# 1-Schematic_Automatic_temperature_humidi.net
KiCad netlist of a schematic drawn in EasyEDA
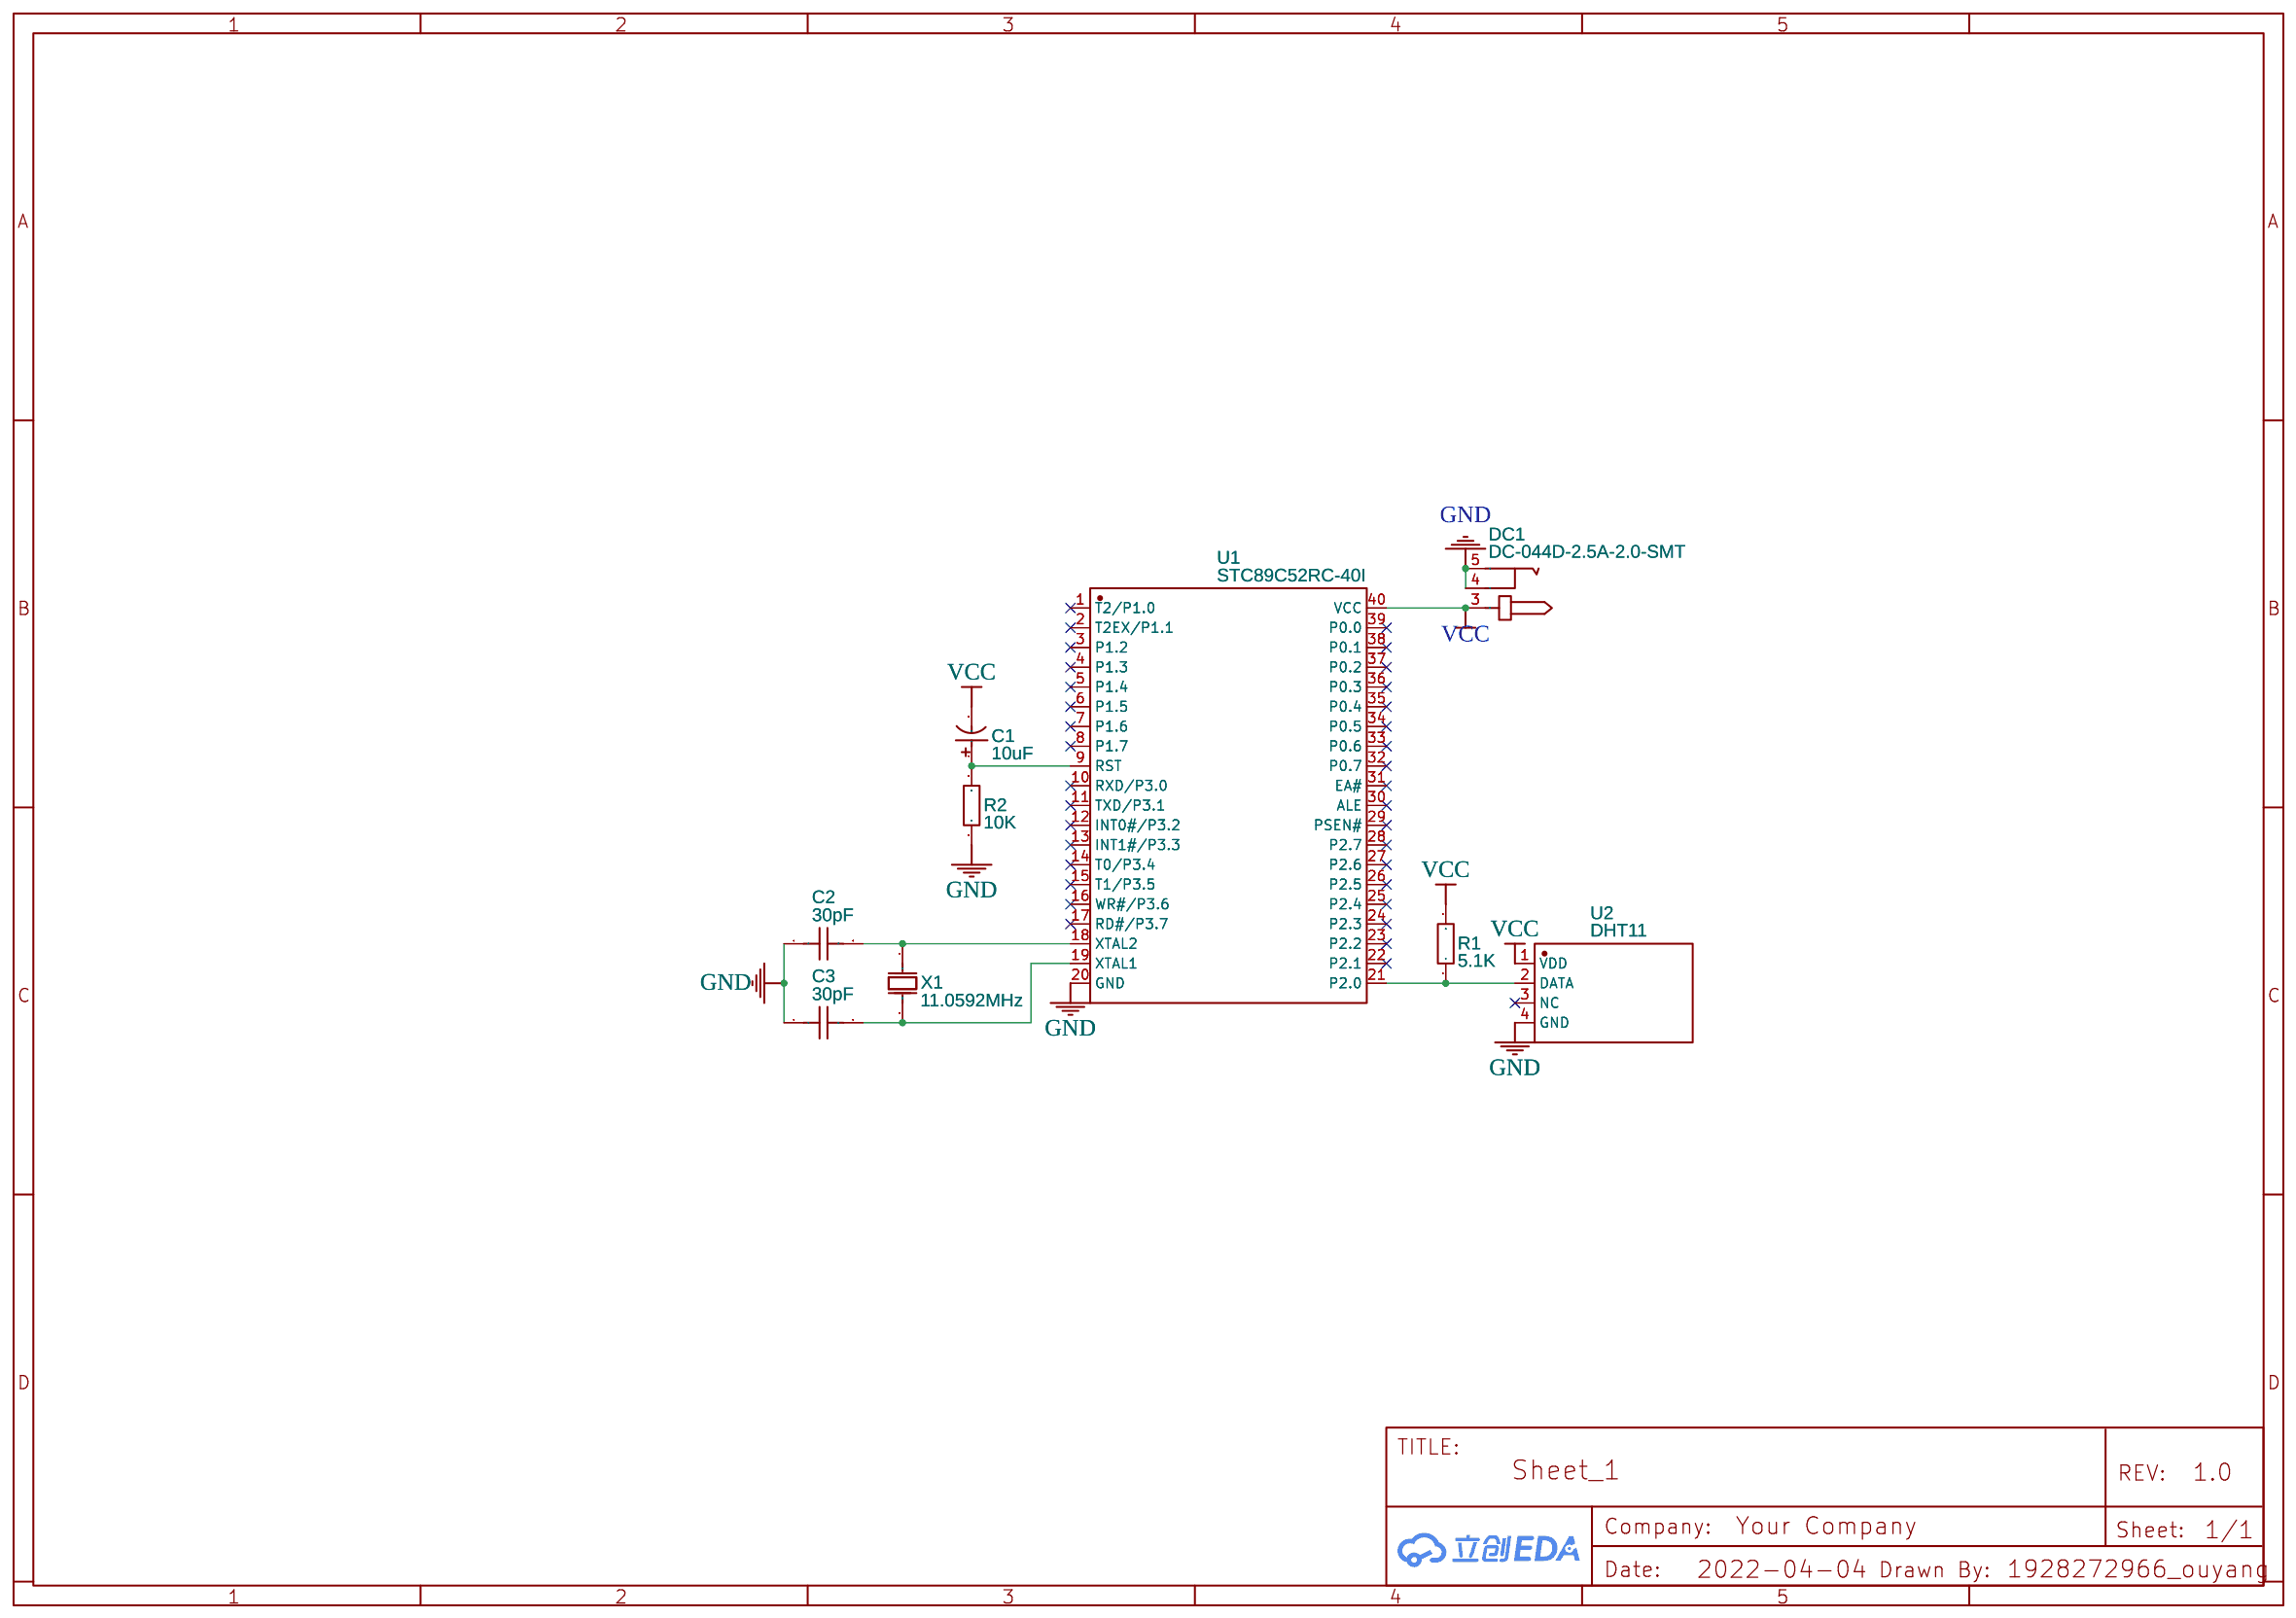
[diagram p0: schematic sheet]

(export (version "E")
  (design (tool "Eeschema 10.0.6"))
  (components
    (comp (ref "C1")
      (value "10uF")
      (fields
        (field (name "BOM_Manufacturer Part") "10uF 16V 3*5")
        (field (name "BOM_Supplier Part") "C43798")
      )
      (libsource (lib "") (part "10uF 16V 3*5"))
    )
    (comp (ref "C2")
      (value "30pF")
      (fields
        (field (name "BOM_Manufacturer Part") "DCC300J20COHF6FJ5A0")
        (field (name "BOM_Supplier Part") "C2896130")
      )
      (libsource (lib "") (part "DCC300J20COHF6FJ5A0"))
    )
    (comp (ref "C3")
      (value "30pF")
      (fields
        (field (name "BOM_Manufacturer Part") "DCC300J20COHF6FJ5A0")
        (field (name "BOM_Supplier Part") "C2896130")
      )
      (libsource (lib "") (part "DCC300J20COHF6FJ5A0"))
    )
    (comp (ref "DC1")
      (value "DC-044D-2.5A-2.0-SMT")
      (fields (field (name "BOM_Supplier Part") "C397342"))
      (libsource (lib "") (part "DC-044D-2.5A-2.0-SMT"))
    )
    (comp (ref "R1")
      (value "5.1K")
      (fields
        (field (name "BOM_Manufacturer Part") "MFR0W4F5101A50")
        (field (name "BOM_Supplier Part") "C58591")
      )
      (libsource (lib "") (part "MFR0W4F5101A50"))
    )
    (comp (ref "R2")
      (value "10K")
      (fields
        (field (name "BOM_Manufacturer Part") "MFR0W4F1002A50")
        (field (name "BOM_Supplier Part") "C57436")
      )
      (libsource (lib "") (part "MFR0W4F1002A50"))
    )
    (comp (ref "U1")
      (value "STC89C52RC-40I")
      (fields (field (name "BOM_Supplier Part") "C14022"))
      (libsource (lib "") (part "STC89C52RC-40I"))
    )
    (comp (ref "U2")
      (value "DHT11")
      (fields (field (name "BOM_Supplier Part") "C117051"))
      (libsource (lib "") (part "DHT11"))
    )
    (comp (ref "X1")
      (value "11.0592MHz")
      (fields
        (field (name "BOM_Manufacturer Part") "X49SD110592MSD2SC")
        (field (name "BOM_Supplier Part") "C2203")
      )
      (libsource (lib "") (part "X49SD110592MSD2SC"))
    )
  )
  (nets
    (net (code "1") (name "GND") (class "Default")
      (node (ref "C2") (pin "1") (pinfunction "1_1") (pintype "unspecified"))
      (node (ref "C3") (pin "1") (pinfunction "1_1") (pintype "unspecified"))
      (node (ref "DC1") (pin "4") (pinfunction "4_4") (pintype "unspecified"))
      (node (ref "DC1") (pin "5") (pinfunction "5_5") (pintype "unspecified"))
      (node (ref "R2") (pin "1") (pinfunction "1_1") (pintype "input"))
      (node (ref "U1") (pin "20") (pinfunction "GND_20") (pintype "unspecified"))
      (node (ref "U2") (pin "4") (pinfunction "GND_4") (pintype "unspecified"))
    )
    (net (code "2") (name "Net-(U1-P2.0)") (class "Default")
      (node (ref "R1") (pin "1") (pinfunction "1_1") (pintype "input"))
      (node (ref "U1") (pin "21") (pinfunction "P2.0_21") (pintype "unspecified"))
      (node (ref "U2") (pin "2") (pinfunction "DATA_2") (pintype "unspecified"))
    )
    (net (code "3") (name "Net-(U1-RST)") (class "Default")
      (node (ref "C1") (pin "1") (pinfunction "1_1") (pintype "input"))
      (node (ref "R2") (pin "2") (pinfunction "2_2") (pintype "input"))
      (node (ref "U1") (pin "9") (pinfunction "RST_9") (pintype "unspecified"))
    )
    (net (code "4") (name "Net-(U1-XTAL1)") (class "Default")
      (node (ref "C3") (pin "2") (pinfunction "2_2") (pintype "unspecified"))
      (node (ref "U1") (pin "19") (pinfunction "XTAL1_19") (pintype "unspecified"))
      (node (ref "X1") (pin "2") (pinfunction "OSC2_2") (pintype "input"))
    )
    (net (code "5") (name "Net-(U1-XTAL2)") (class "Default")
      (node (ref "C2") (pin "2") (pinfunction "2_2") (pintype "unspecified"))
      (node (ref "U1") (pin "18") (pinfunction "XTAL2_18") (pintype "unspecified"))
      (node (ref "X1") (pin "1") (pinfunction "OSC1_1") (pintype "input"))
    )
    (net (code "6") (name "VCC") (class "Default")
      (node (ref "C1") (pin "2") (pinfunction "2_2") (pintype "input"))
      (node (ref "DC1") (pin "3") (pinfunction "3_3") (pintype "unspecified"))
      (node (ref "R1") (pin "2") (pinfunction "2_2") (pintype "input"))
      (node (ref "U1") (pin "40") (pinfunction "VCC_40") (pintype "unspecified"))
      (node (ref "U2") (pin "1") (pinfunction "VDD_1") (pintype "unspecified"))
    )
    (net (code "7") (name "unconnected-(U1-ALE-Pad30)") (class "Default")
      (node (ref "U1") (pin "30") (pinfunction "ALE_30") (pintype "unspecified+no_connect"))
    )
    (net (code "8") (name "unconnected-(U1-EA#-Pad31)") (class "Default")
      (node (ref "U1") (pin "31") (pinfunction "EA#_31") (pintype "unspecified+no_connect"))
    )
    (net (code "9") (name "unconnected-(U1-INT0#{slash}P3.2-Pad12)") (class "Default")
      (node (ref "U1") (pin "12") (pinfunction "INT0#/P3.2_12") (pintype "unspecified+no_connect"))
    )
    (net (code "10") (name "unconnected-(U1-INT1#{slash}P3.3-Pad13)") (class "Default")
      (node (ref "U1") (pin "13") (pinfunction "INT1#/P3.3_13") (pintype "unspecified+no_connect"))
    )
    (net (code "11") (name "unconnected-(U1-P0.0-Pad39)") (class "Default")
      (node (ref "U1") (pin "39") (pinfunction "P0.0_39") (pintype "unspecified+no_connect"))
    )
    (net (code "12") (name "unconnected-(U1-P0.1-Pad38)") (class "Default")
      (node (ref "U1") (pin "38") (pinfunction "P0.1_38") (pintype "unspecified+no_connect"))
    )
    (net (code "13") (name "unconnected-(U1-P0.2-Pad37)") (class "Default")
      (node (ref "U1") (pin "37") (pinfunction "P0.2_37") (pintype "unspecified+no_connect"))
    )
    (net (code "14") (name "unconnected-(U1-P0.3-Pad36)") (class "Default")
      (node (ref "U1") (pin "36") (pinfunction "P0.3_36") (pintype "unspecified+no_connect"))
    )
    (net (code "15") (name "unconnected-(U1-P0.4-Pad35)") (class "Default")
      (node (ref "U1") (pin "35") (pinfunction "P0.4_35") (pintype "unspecified+no_connect"))
    )
    (net (code "16") (name "unconnected-(U1-P0.5-Pad34)") (class "Default")
      (node (ref "U1") (pin "34") (pinfunction "P0.5_34") (pintype "unspecified+no_connect"))
    )
    (net (code "17") (name "unconnected-(U1-P0.6-Pad33)") (class "Default")
      (node (ref "U1") (pin "33") (pinfunction "P0.6_33") (pintype "unspecified+no_connect"))
    )
    (net (code "18") (name "unconnected-(U1-P0.7-Pad32)") (class "Default")
      (node (ref "U1") (pin "32") (pinfunction "P0.7_32") (pintype "unspecified+no_connect"))
    )
    (net (code "19") (name "unconnected-(U1-P1.2-Pad3)") (class "Default")
      (node (ref "U1") (pin "3") (pinfunction "P1.2_3") (pintype "unspecified+no_connect"))
    )
    (net (code "20") (name "unconnected-(U1-P1.3-Pad4)") (class "Default")
      (node (ref "U1") (pin "4") (pinfunction "P1.3_4") (pintype "unspecified+no_connect"))
    )
    (net (code "21") (name "unconnected-(U1-P1.4-Pad5)") (class "Default")
      (node (ref "U1") (pin "5") (pinfunction "P1.4_5") (pintype "unspecified+no_connect"))
    )
    (net (code "22") (name "unconnected-(U1-P1.5-Pad6)") (class "Default")
      (node (ref "U1") (pin "6") (pinfunction "P1.5_6") (pintype "unspecified+no_connect"))
    )
    (net (code "23") (name "unconnected-(U1-P1.6-Pad7)") (class "Default")
      (node (ref "U1") (pin "7") (pinfunction "P1.6_7") (pintype "unspecified+no_connect"))
    )
    (net (code "24") (name "unconnected-(U1-P1.7-Pad8)") (class "Default")
      (node (ref "U1") (pin "8") (pinfunction "P1.7_8") (pintype "unspecified+no_connect"))
    )
    (net (code "25") (name "unconnected-(U1-P2.1-Pad22)") (class "Default")
      (node (ref "U1") (pin "22") (pinfunction "P2.1_22") (pintype "unspecified+no_connect"))
    )
    (net (code "26") (name "unconnected-(U1-P2.2-Pad23)") (class "Default")
      (node (ref "U1") (pin "23") (pinfunction "P2.2_23") (pintype "unspecified+no_connect"))
    )
    (net (code "27") (name "unconnected-(U1-P2.3-Pad24)") (class "Default")
      (node (ref "U1") (pin "24") (pinfunction "P2.3_24") (pintype "unspecified+no_connect"))
    )
    (net (code "28") (name "unconnected-(U1-P2.4-Pad25)") (class "Default")
      (node (ref "U1") (pin "25") (pinfunction "P2.4_25") (pintype "unspecified+no_connect"))
    )
    (net (code "29") (name "unconnected-(U1-P2.5-Pad26)") (class "Default")
      (node (ref "U1") (pin "26") (pinfunction "P2.5_26") (pintype "unspecified+no_connect"))
    )
    (net (code "30") (name "unconnected-(U1-P2.6-Pad27)") (class "Default")
      (node (ref "U1") (pin "27") (pinfunction "P2.6_27") (pintype "unspecified+no_connect"))
    )
    (net (code "31") (name "unconnected-(U1-P2.7-Pad28)") (class "Default")
      (node (ref "U1") (pin "28") (pinfunction "P2.7_28") (pintype "unspecified+no_connect"))
    )
    (net (code "32") (name "unconnected-(U1-PSEN#-Pad29)") (class "Default")
      (node (ref "U1") (pin "29") (pinfunction "PSEN#_29") (pintype "unspecified+no_connect"))
    )
    (net (code "33") (name "unconnected-(U1-RD#{slash}P3.7-Pad17)") (class "Default")
      (node (ref "U1") (pin "17") (pinfunction "RD#/P3.7_17") (pintype "unspecified+no_connect"))
    )
    (net (code "34") (name "unconnected-(U1-RXD{slash}P3.0-Pad10)") (class "Default")
      (node (ref "U1") (pin "10") (pinfunction "RXD/P3.0_10") (pintype "unspecified+no_connect"))
    )
    (net (code "35") (name "unconnected-(U1-T0{slash}P3.4-Pad14)") (class "Default")
      (node (ref "U1") (pin "14") (pinfunction "T0/P3.4_14") (pintype "unspecified+no_connect"))
    )
    (net (code "36") (name "unconnected-(U1-T1{slash}P3.5-Pad15)") (class "Default")
      (node (ref "U1") (pin "15") (pinfunction "T1/P3.5_15") (pintype "unspecified+no_connect"))
    )
    (net (code "37") (name "unconnected-(U1-T2EX{slash}P1.1-Pad2)") (class "Default")
      (node (ref "U1") (pin "2") (pinfunction "T2EX/P1.1_2") (pintype "unspecified+no_connect"))
    )
    (net (code "38") (name "unconnected-(U1-T2{slash}P1.0-Pad1)") (class "Default")
      (node (ref "U1") (pin "1") (pinfunction "T2/P1.0_1") (pintype "unspecified+no_connect"))
    )
    (net (code "39") (name "unconnected-(U1-TXD{slash}P3.1-Pad11)") (class "Default")
      (node (ref "U1") (pin "11") (pinfunction "TXD/P3.1_11") (pintype "unspecified+no_connect"))
    )
    (net (code "40") (name "unconnected-(U1-WR#{slash}P3.6-Pad16)") (class "Default")
      (node (ref "U1") (pin "16") (pinfunction "WR#/P3.6_16") (pintype "unspecified+no_connect"))
    )
    (net (code "41") (name "unconnected-(U2-NC-Pad3)") (class "Default")
      (node (ref "U2") (pin "3") (pinfunction "NC_3") (pintype "unspecified+no_connect"))
    )
  )
)
